# controller.net
KiCad netlist of a schematic drawn in Altium Designer
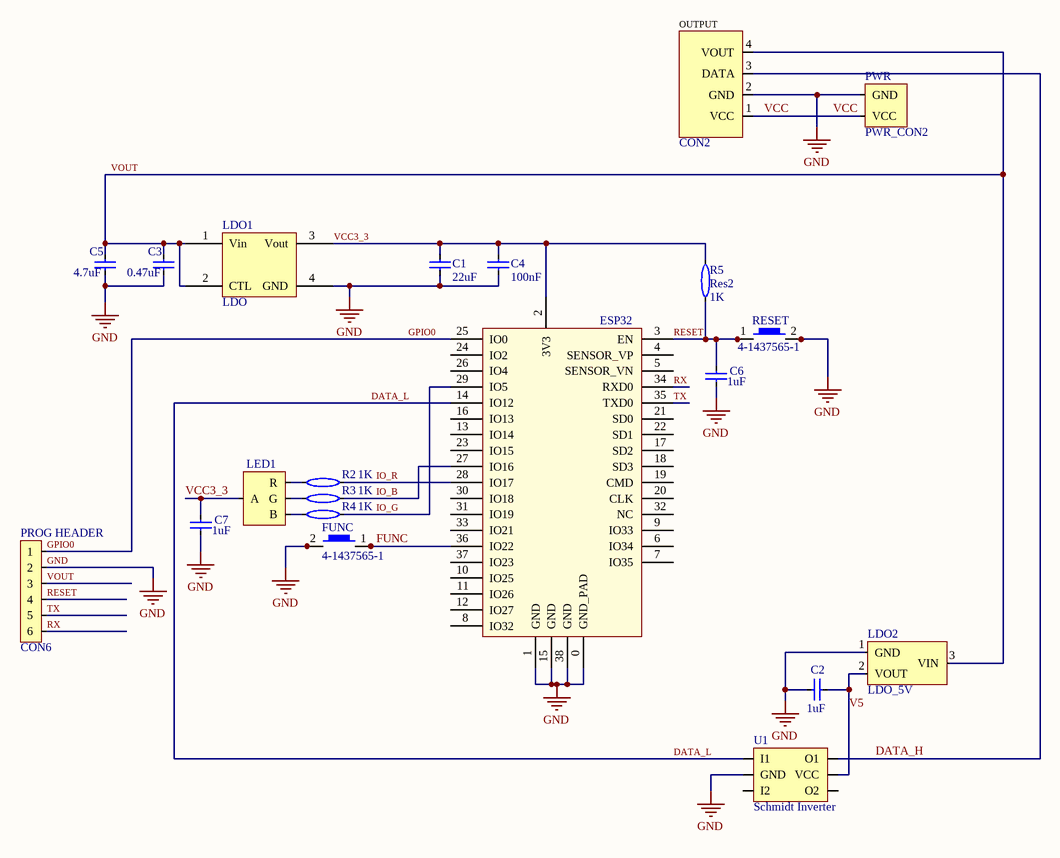
[diagram p0: controller.SchDoc]

(export (version "E")
  (design (tool "Eeschema 10.0.6"))
  (components
    (comp (ref "C1")
      (value "22uF")
      (footprint "CAPC_1206_3216X16L")
      (description "Capacitor")
      (fields (field (name "Comment") "Cap") (field (name "PUBLISHER") "Altium Limited"))
      (libsource (lib "buck2") (part "Cap"))
    )
    (comp (ref "C2")
      (value "1uF")
      (footprint "CAPC_0603_1608X08L")
      (description "Capacitor")
      (fields (field (name "Comment") "Cap") (field (name "PUBLISHER") "Altium Limited"))
      (libsource (lib "buck2") (part "Cap"))
    )
    (comp (ref "C3")
      (value "0.47uF")
      (footprint "CAPC_0603_1608X08L")
      (description "Capacitor")
      (fields (field (name "Comment") "Cap") (field (name "PUBLISHER") "Altium Limited"))
      (libsource (lib "buck2") (part "Cap"))
    )
    (comp (ref "C4")
      (value "100nF")
      (footprint "CAPC_0603_1608X08L")
      (description "Capacitor")
      (fields (field (name "Comment") "Cap") (field (name "PUBLISHER") "Altium Limited"))
      (libsource (lib "buck2") (part "Cap"))
    )
    (comp (ref "C5")
      (value "4.7uF")
      (footprint "CAPC_1206_3216X16L")
      (description "Capacitor")
      (fields (field (name "Comment") "Cap") (field (name "PUBLISHER") "Altium Limited"))
      (libsource (lib "buck2") (part "Cap"))
    )
    (comp (ref "C6")
      (value "1uF")
      (footprint "CAPC_0603_1608X08L")
      (description "Capacitor")
      (fields (field (name "Comment") "Cap") (field (name "PUBLISHER") "Altium Limited"))
      (libsource (lib "TideTracker") (part "Cap"))
    )
    (comp (ref "C7")
      (value "1uF")
      (footprint "CAPC_0603_1608X08L")
      (description "Capacitor")
      (fields (field (name "Comment") "Cap") (field (name "PUBLISHER") "Altium Limited"))
      (libsource (lib "TideTracker") (part "Cap"))
    )
    (comp (ref "ESP32")
      (value "ESP32S_Module")
      (footprint "ESP32S")
      (description "Esp-32S")
      (libsource (lib "buck2") (part "ESP32S_Module"))
    )
    (comp (ref "FUNC")
      (value "4-1437565-1")
      (footprint "FSM-SWITCH")
      (description "6x6mm SMD tactile switch,5mm H 1.6N Black Button Tactile Switch, SPST-NO 0.05 A@ 12 V dc 1.4mm")
      (fields (field (name "RS PART NUMBER") "1616046"))
      (libsource (lib "") (part "4-1437565-1_1"))
    )
    (comp (ref "LDO1")
      (value "LDO")
      (footprint "buck2:SOT230P700X180-4N")
      (description "LDO Voltage Regulator")
      (libsource (lib "buck2") (part "LDO"))
    )
    (comp (ref "LDO2")
      (value "LDO_5V")
      (footprint "SOT23")
      (description "Microchip MCP1700T-5002E/TT, LDO Regulator, 250mA, 5 V")
      (libsource (lib "buck2") (part "LDO_5V"))
    )
    (comp (ref "LED1")
      (value "RGB_LED")
      (footprint "PLCC-4")
      (description "dot marks common anode")
      (libsource (lib "buck2") (part "RGB_LED"))
    )
    (comp (ref "OUTPUT") (value "CON2") (footprint "CONNECTOR") (libsource (lib "buck2") (part "CON2")))
    (comp (ref "PROG HEADER") (value "CON6") (footprint "CON2X3") (libsource (lib "buck2") (part "CON6")))
    (comp (ref "PWR") (value "PWR_CON2") (footprint "PWR_CON2") (libsource (lib "buck2") (part "PWR_CON2")))
    (comp (ref "R2")
      (value "1K")
      (footprint "RESC_0603_1608X08L")
      (description "Resistor")
      (fields (field (name "PUBLISHER") "Altium Limited"))
      (libsource (lib "buck2") (part "Res2"))
    )
    (comp (ref "R3")
      (value "1K")
      (footprint "RESC_0603_1608X08L")
      (description "Resistor")
      (fields (field (name "PUBLISHER") "Altium Limited"))
      (libsource (lib "buck2") (part "Res2"))
    )
    (comp (ref "R4")
      (value "1K")
      (footprint "RESC_0603_1608X08L")
      (description "Resistor")
      (fields (field (name "PUBLISHER") "Altium Limited"))
      (libsource (lib "buck2") (part "Res2"))
    )
    (comp (ref "R5")
      (value "Res2")
      (footprint "RESC_0603_1608X08L")
      (description "Resistor")
      (fields (field (name "ALTIUM_VALUE") "1K") (field (name "PUBLISHER") "Altium Limited"))
      (libsource (lib "buck2") (part "Res2"))
    )
    (comp (ref "RESET")
      (value "4-1437565-1")
      (footprint "FSM-SWITCH")
      (description "6x6mm SMD tactile switch,5mm H 1.6N Black Button Tactile Switch, SPST-NO 0.05 A@ 12 V dc 1.4mm")
      (fields (field (name "RS PART NUMBER") "1616046"))
      (libsource (lib "buck2") (part "4-1437565-1"))
    )
    (comp (ref "U1")
      (value "Schmidt Inverter")
      (footprint "SOT65P210X110-6L")
      (description "ON Semiconductor NLV27WZ14DFT2G")
      (libsource (lib "buck2") (part "Schmidt Inverter"))
    )
  )
  (nets
    (net (code "1") (name "/DATA_H") (class "Default")
      (node (ref "OUTPUT") (pin "3") (pinfunction "DATA_3") (pintype "passive"))
      (node (ref "U1") (pin "6") (pinfunction "O1_6") (pintype "passive"))
    )
    (net (code "2") (name "/DATA_L") (class "Default")
      (node (ref "ESP32") (pin "14") (pinfunction "IO12_14") (pintype "passive"))
      (node (ref "U1") (pin "1") (pinfunction "I1_1") (pintype "passive"))
    )
    (net (code "3") (name "/FUNC") (class "Default")
      (node (ref "ESP32") (pin "36") (pinfunction "IO22_36") (pintype "passive"))
      (node (ref "FUNC") (pin "1") (pinfunction "1_1") (pintype "passive"))
      (node (ref "FUNC") (pin "3") (pinfunction "3_3") (pintype "passive"))
    )
    (net (code "4") (name "/GPIO0") (class "Default")
      (node (ref "ESP32") (pin "25") (pinfunction "IO0_25") (pintype "passive"))
      (node (ref "PROG HEADER") (pin "1") (pinfunction "1_1") (pintype "passive"))
    )
    (net (code "5") (name "/IO_B") (class "Default")
      (node (ref "ESP32") (pin "27") (pinfunction "IO16_27") (pintype "passive"))
      (node (ref "R3") (pin "2") (pinfunction "2_2") (pintype "passive"))
    )
    (net (code "6") (name "/IO_G") (class "Default")
      (node (ref "ESP32") (pin "29") (pinfunction "IO5_29") (pintype "passive"))
      (node (ref "R4") (pin "2") (pinfunction "2_2") (pintype "passive"))
    )
    (net (code "7") (name "/IO_R") (class "Default")
      (node (ref "ESP32") (pin "28") (pinfunction "IO17_28") (pintype "passive"))
      (node (ref "R2") (pin "2") (pinfunction "2_2") (pintype "passive"))
    )
    (net (code "8") (name "/RESET") (class "Default")
      (node (ref "C6") (pin "2") (pinfunction "2_2") (pintype "passive"))
      (node (ref "ESP32") (pin "3") (pinfunction "EN_3") (pintype "power_in"))
      (node (ref "PROG HEADER") (pin "4") (pinfunction "4_4") (pintype "passive"))
      (node (ref "R5") (pin "1") (pinfunction "1_1") (pintype "passive"))
      (node (ref "RESET") (pin "1") (pinfunction "1_1") (pintype "passive"))
      (node (ref "RESET") (pin "3") (pinfunction "3_3") (pintype "passive"))
    )
    (net (code "9") (name "/RX") (class "Default")
      (node (ref "ESP32") (pin "34") (pinfunction "RXD0_34") (pintype "passive"))
      (node (ref "PROG HEADER") (pin "6") (pinfunction "6_6") (pintype "passive"))
    )
    (net (code "10") (name "/TX") (class "Default")
      (node (ref "ESP32") (pin "35") (pinfunction "TXD0_35") (pintype "passive"))
      (node (ref "PROG HEADER") (pin "5") (pinfunction "5_5") (pintype "passive"))
    )
    (net (code "11") (name "/V5") (class "Default")
      (node (ref "C2") (pin "2") (pinfunction "2_2") (pintype "passive"))
      (node (ref "LDO2") (pin "2") (pinfunction "VOUT_2") (pintype "passive"))
      (node (ref "U1") (pin "5") (pinfunction "VCC_5") (pintype "passive"))
    )
    (net (code "12") (name "/VCC") (class "Default")
      (node (ref "OUTPUT") (pin "1") (pinfunction "VCC_1") (pintype "passive"))
      (node (ref "PWR") (pin "1") (pinfunction "VCC_1") (pintype "passive"))
    )
    (net (code "13") (name "/VCC3_3") (class "Default")
      (node (ref "C1") (pin "2") (pinfunction "2_2") (pintype "passive"))
      (node (ref "C4") (pin "2") (pinfunction "2_2") (pintype "passive"))
      (node (ref "C7") (pin "2") (pinfunction "2_2") (pintype "passive"))
      (node (ref "ESP32") (pin "2") (pinfunction "3V3_2") (pintype "power_in"))
      (node (ref "LDO1") (pin "3") (pinfunction "Vout_3") (pintype "passive"))
      (node (ref "LED1") (pin "2") (pinfunction "A_2") (pintype "passive"))
      (node (ref "R5") (pin "2") (pinfunction "2_2") (pintype "passive"))
    )
    (net (code "14") (name "/VOUT") (class "Default")
      (node (ref "C3") (pin "2") (pinfunction "2_2") (pintype "passive"))
      (node (ref "C5") (pin "2") (pinfunction "2_2") (pintype "passive"))
      (node (ref "LDO1") (pin "1") (pinfunction "Vin_1") (pintype "passive"))
      (node (ref "LDO1") (pin "2") (pinfunction "CTL_2") (pintype "passive"))
      (node (ref "LDO2") (pin "3") (pinfunction "VIN_3") (pintype "passive"))
      (node (ref "OUTPUT") (pin "4") (pinfunction "VOUT_4") (pintype "passive"))
      (node (ref "PROG HEADER") (pin "3") (pinfunction "3_3") (pintype "passive"))
    )
    (net (code "15") (name "GND") (class "Default")
      (node (ref "C1") (pin "1") (pinfunction "1_1") (pintype "passive"))
      (node (ref "C2") (pin "1") (pinfunction "1_1") (pintype "passive"))
      (node (ref "C3") (pin "1") (pinfunction "1_1") (pintype "passive"))
      (node (ref "C4") (pin "1") (pinfunction "1_1") (pintype "passive"))
      (node (ref "C5") (pin "1") (pinfunction "1_1") (pintype "passive"))
      (node (ref "C6") (pin "1") (pinfunction "1_1") (pintype "passive"))
      (node (ref "C7") (pin "1") (pinfunction "1_1") (pintype "passive"))
      (node (ref "ESP32") (pin "0") (pinfunction "GND_PAD_0") (pintype "power_in"))
      (node (ref "ESP32") (pin "1") (pinfunction "GND_1") (pintype "power_in"))
      (node (ref "ESP32") (pin "15") (pinfunction "GND_15") (pintype "power_in"))
      (node (ref "ESP32") (pin "38") (pinfunction "GND_38") (pintype "power_in"))
      (node (ref "FUNC") (pin "2") (pinfunction "2_2") (pintype "passive"))
      (node (ref "FUNC") (pin "4") (pinfunction "4_4") (pintype "passive"))
      (node (ref "LDO1") (pin "4") (pinfunction "GND_4") (pintype "passive"))
      (node (ref "LDO2") (pin "1") (pinfunction "GND_1") (pintype "passive"))
      (node (ref "OUTPUT") (pin "2") (pinfunction "GND_2") (pintype "passive"))
      (node (ref "PROG HEADER") (pin "2") (pinfunction "2_2") (pintype "passive"))
      (node (ref "PWR") (pin "2") (pinfunction "GND_2") (pintype "passive"))
      (node (ref "RESET") (pin "2") (pinfunction "2_2") (pintype "passive"))
      (node (ref "RESET") (pin "4") (pinfunction "4_4") (pintype "passive"))
      (node (ref "U1") (pin "2") (pinfunction "GND_2") (pintype "passive"))
    )
    (net (code "16") (name "Net-(LED1-B)") (class "Default")
      (node (ref "LED1") (pin "4") (pinfunction "B_4") (pintype "passive"))
      (node (ref "R4") (pin "1") (pinfunction "1_1") (pintype "passive"))
    )
    (net (code "17") (name "Net-(LED1-G)") (class "Default")
      (node (ref "LED1") (pin "3") (pinfunction "G_3") (pintype "passive"))
      (node (ref "R3") (pin "1") (pinfunction "1_1") (pintype "passive"))
    )
    (net (code "18") (name "Net-(LED1-R)") (class "Default")
      (node (ref "LED1") (pin "1") (pinfunction "R_1") (pintype "passive"))
      (node (ref "R2") (pin "1") (pinfunction "1_1") (pintype "passive"))
    )
    (net (code "19") (name "unconnected-(ESP32-CLK-Pad20)") (class "Default")
      (node (ref "ESP32") (pin "20") (pinfunction "CLK_20") (pintype "passive"))
    )
    (net (code "20") (name "unconnected-(ESP32-CMD-Pad19)") (class "Default")
      (node (ref "ESP32") (pin "19") (pinfunction "CMD_19") (pintype "passive"))
    )
    (net (code "21") (name "unconnected-(ESP32-IO2-Pad24)") (class "Default")
      (node (ref "ESP32") (pin "24") (pinfunction "IO2_24") (pintype "passive"))
    )
    (net (code "22") (name "unconnected-(ESP32-IO4-Pad26)") (class "Default")
      (node (ref "ESP32") (pin "26") (pinfunction "IO4_26") (pintype "passive"))
    )
    (net (code "23") (name "unconnected-(ESP32-IO13-Pad16)") (class "Default")
      (node (ref "ESP32") (pin "16") (pinfunction "IO13_16") (pintype "passive"))
    )
    (net (code "24") (name "unconnected-(ESP32-IO14-Pad13)") (class "Default")
      (node (ref "ESP32") (pin "13") (pinfunction "IO14_13") (pintype "passive"))
    )
    (net (code "25") (name "unconnected-(ESP32-IO15-Pad23)") (class "Default")
      (node (ref "ESP32") (pin "23") (pinfunction "IO15_23") (pintype "passive"))
    )
    (net (code "26") (name "unconnected-(ESP32-IO18-Pad30)") (class "Default")
      (node (ref "ESP32") (pin "30") (pinfunction "IO18_30") (pintype "passive"))
    )
    (net (code "27") (name "unconnected-(ESP32-IO19-Pad31)") (class "Default")
      (node (ref "ESP32") (pin "31") (pinfunction "IO19_31") (pintype "passive"))
    )
    (net (code "28") (name "unconnected-(ESP32-IO21-Pad33)") (class "Default")
      (node (ref "ESP32") (pin "33") (pinfunction "IO21_33") (pintype "passive"))
    )
    (net (code "29") (name "unconnected-(ESP32-IO23-Pad37)") (class "Default")
      (node (ref "ESP32") (pin "37") (pinfunction "IO23_37") (pintype "passive"))
    )
    (net (code "30") (name "unconnected-(ESP32-IO25-Pad10)") (class "Default")
      (node (ref "ESP32") (pin "10") (pinfunction "IO25_10") (pintype "passive"))
    )
    (net (code "31") (name "unconnected-(ESP32-IO26-Pad11)") (class "Default")
      (node (ref "ESP32") (pin "11") (pinfunction "IO26_11") (pintype "passive"))
    )
    (net (code "32") (name "unconnected-(ESP32-IO27-Pad12)") (class "Default")
      (node (ref "ESP32") (pin "12") (pinfunction "IO27_12") (pintype "passive"))
    )
    (net (code "33") (name "unconnected-(ESP32-IO32-Pad8)") (class "Default")
      (node (ref "ESP32") (pin "8") (pinfunction "IO32_8") (pintype "passive"))
    )
    (net (code "34") (name "unconnected-(ESP32-IO33-Pad9)") (class "Default")
      (node (ref "ESP32") (pin "9") (pinfunction "IO33_9") (pintype "passive"))
    )
    (net (code "35") (name "unconnected-(ESP32-IO34-Pad6)") (class "Default")
      (node (ref "ESP32") (pin "6") (pinfunction "IO34_6") (pintype "passive"))
    )
    (net (code "36") (name "unconnected-(ESP32-IO35-Pad7)") (class "Default")
      (node (ref "ESP32") (pin "7") (pinfunction "IO35_7") (pintype "passive"))
    )
    (net (code "37") (name "unconnected-(ESP32-NC-Pad32)") (class "Default")
      (node (ref "ESP32") (pin "32") (pinfunction "NC_32") (pintype "passive"))
    )
    (net (code "38") (name "unconnected-(ESP32-SD0-Pad21)") (class "Default")
      (node (ref "ESP32") (pin "21") (pinfunction "SD0_21") (pintype "passive"))
    )
    (net (code "39") (name "unconnected-(ESP32-SD1-Pad22)") (class "Default")
      (node (ref "ESP32") (pin "22") (pinfunction "SD1_22") (pintype "passive"))
    )
    (net (code "40") (name "unconnected-(ESP32-SD2-Pad17)") (class "Default")
      (node (ref "ESP32") (pin "17") (pinfunction "SD2_17") (pintype "passive"))
    )
    (net (code "41") (name "unconnected-(ESP32-SD3-Pad18)") (class "Default")
      (node (ref "ESP32") (pin "18") (pinfunction "SD3_18") (pintype "passive"))
    )
    (net (code "42") (name "unconnected-(ESP32-SENSOR_VN-Pad5)") (class "Default")
      (node (ref "ESP32") (pin "5") (pinfunction "SENSOR_VN_5") (pintype "passive"))
    )
    (net (code "43") (name "unconnected-(ESP32-SENSOR_VP-Pad4)") (class "Default")
      (node (ref "ESP32") (pin "4") (pinfunction "SENSOR_VP_4") (pintype "passive"))
    )
    (net (code "44") (name "unconnected-(U1-I2-Pad3)") (class "Default")
      (node (ref "U1") (pin "3") (pinfunction "I2_3") (pintype "passive"))
    )
    (net (code "45") (name "unconnected-(U1-O2-Pad4)") (class "Default")
      (node (ref "U1") (pin "4") (pinfunction "O2_4") (pintype "passive"))
    )
  )
)
